# Dogfish3D_-_Endstop_Channel.net
KiCad netlist of a schematic drawn in Altium Designer
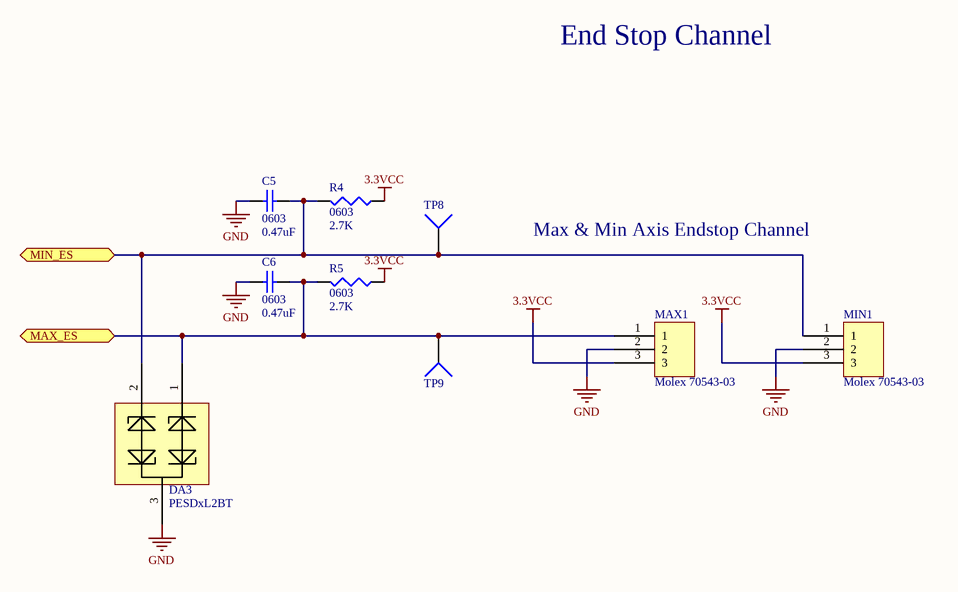
[diagram p0: Dogfish3D - Endstop Channel.SchDoc]

(export (version "E")
  (design (tool "Eeschema 10.0.6"))
  (components
    (comp (ref "C5")
      (value "0603")
      (footprint "1608[0603]")
      (description "Capacitor (Semiconductor SIM Model)")
      (fields (field (name "ALTIUM_VALUE") "0.47uF") (field (name "PUBLISHER") "Altium Limited"))
      (libsource (lib "Miscellaneous Devices") (part "Cap Semi"))
    )
    (comp (ref "C6")
      (value "0603")
      (footprint "1608[0603]")
      (description "Capacitor (Semiconductor SIM Model)")
      (fields (field (name "ALTIUM_VALUE") "0.47uF") (field (name "PUBLISHER") "Altium Limited"))
      (libsource (lib "Miscellaneous Devices") (part "Cap Semi"))
    )
    (comp (ref "DA3")
      (value "PESDxL2BT")
      (footprint "SOT95P230X110-3N")
      (description "PESDxL2BT TVS Diode Array 2x")
      (libsource (lib "ZMBo Schematic Library") (part "PESDxL2BT"))
    )
    (comp (ref "MAX1")
      (value "Molex 70543-03")
      (footprint "70543-03")
      (libsource (lib "RADMBo Schematic Library") (part "Molex Endstop"))
    )
    (comp (ref "MIN1")
      (value "Molex 70543-03")
      (footprint "70543-03")
      (libsource (lib "RADMBo Schematic Library") (part "Molex Endstop"))
    )
    (comp (ref "R4")
      (value "0603")
      (footprint "J1-0603")
      (description "Resistor")
      (fields (field (name "ALTIUM_VALUE") "2.7K") (field (name "PUBLISHER") "Altium Limited"))
      (libsource (lib "Miscellaneous Devices") (part "Res3"))
    )
    (comp (ref "R5")
      (value "0603")
      (footprint "J1-0603")
      (description "Resistor")
      (fields (field (name "ALTIUM_VALUE") "2.7K") (field (name "PUBLISHER") "Altium Limited"))
      (libsource (lib "Miscellaneous Devices") (part "Res3"))
    )
    (comp (ref "TP8")
      (value "TP4")
      (footprint "TP-2")
      (description "Socket")
      (fields (field (name "PUBLISHER") "Altium Limited"))
      (libsource (lib "ZMBo Schematic Library") (part "Socket"))
    )
    (comp (ref "TP9")
      (value "TP4")
      (footprint "TP-2")
      (description "Socket")
      (fields (field (name "PUBLISHER") "Altium Limited"))
      (libsource (lib "ZMBo Schematic Library") (part "Socket"))
    )
  )
  (nets
    (net (code "1") (name "/MAX_ES") (class "Default")
      (node (ref "C6") (pin "1") (pinfunction "1_1") (pintype "passive"))
      (node (ref "DA3") (pin "1") (pinfunction "1_1") (pintype "passive"))
      (node (ref "MAX1") (pin "1") (pinfunction "1_1") (pintype "passive"))
      (node (ref "R5") (pin "2") (pinfunction "2_2") (pintype "passive"))
      (node (ref "TP9") (pin "1") (pinfunction "1_1") (pintype "passive"))
    )
    (net (code "2") (name "/MIN_ES") (class "Default")
      (node (ref "C5") (pin "1") (pinfunction "1_1") (pintype "passive"))
      (node (ref "DA3") (pin "2") (pinfunction "2_2") (pintype "passive"))
      (node (ref "MIN1") (pin "1") (pinfunction "1_1") (pintype "passive"))
      (node (ref "R4") (pin "2") (pinfunction "2_2") (pintype "passive"))
      (node (ref "TP8") (pin "1") (pinfunction "1_1") (pintype "passive"))
    )
    (net (code "3") (name "3.3VCC") (class "Default")
      (node (ref "MAX1") (pin "3") (pinfunction "3_3") (pintype "passive"))
      (node (ref "MIN1") (pin "3") (pinfunction "3_3") (pintype "passive"))
      (node (ref "R4") (pin "1") (pinfunction "1_1") (pintype "passive"))
      (node (ref "R5") (pin "1") (pinfunction "1_1") (pintype "passive"))
    )
    (net (code "4") (name "GND") (class "Default")
      (node (ref "C5") (pin "2") (pinfunction "2_2") (pintype "passive"))
      (node (ref "C6") (pin "2") (pinfunction "2_2") (pintype "passive"))
      (node (ref "DA3") (pin "3") (pinfunction "3_3") (pintype "passive"))
      (node (ref "MAX1") (pin "2") (pinfunction "2_2") (pintype "passive"))
      (node (ref "MIN1") (pin "2") (pinfunction "2_2") (pintype "passive"))
    )
  )
)
